# IsolationSheet.net
KiCad netlist of a schematic drawn in Altium Designer
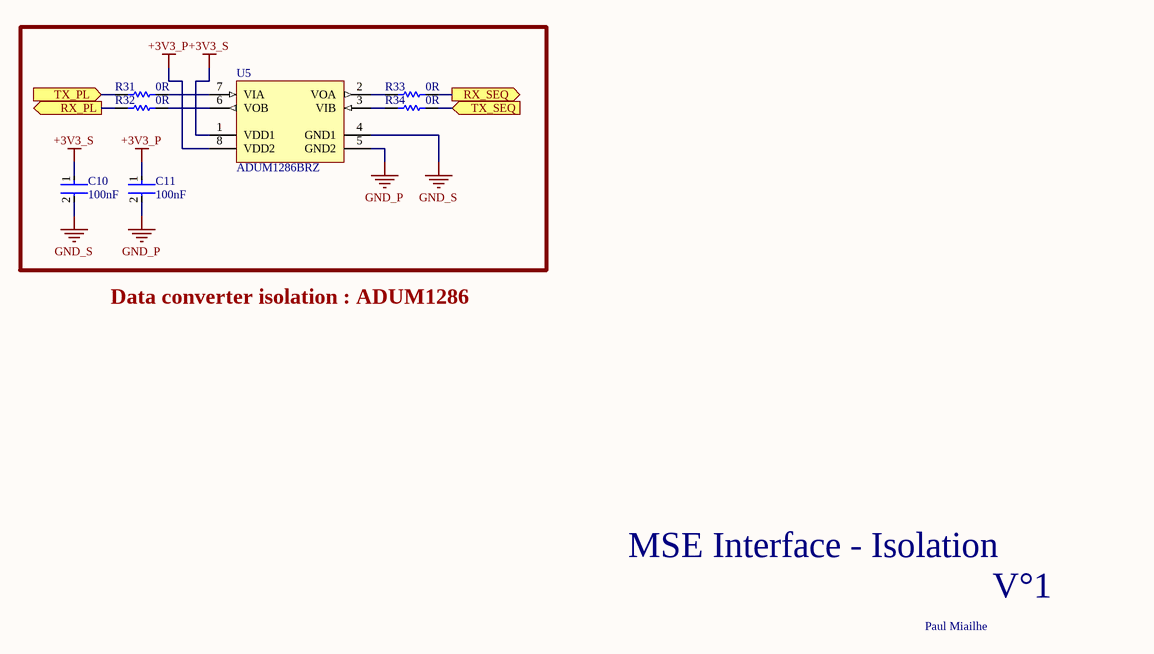
[diagram p0: IsolationSheet.SchDoc]

(export (version "E")
  (design (tool "Eeschema 10.0.6"))
  (components
    (comp (ref "C10")
      (value "CGA3E2X7R1E104K080AA")
      (footprint "FP-CGA3E-0_3-0_1-MFG")
      (description "Cap Ceramic 100nF 25V X7R 10% Pad SMD 0603 +125°C Automotive T/R")
      (fields
        (field (name "CAPACITANCE") "100nF")
        (field (name "TOLERANCE") "10%")
        (field (name "MANUFACTURER") "TDK")
      )
      (libsource (lib "Altium Content Vault") (part "b4654b650e69147ec39a6b967a45e02"))
    )
    (comp (ref "C11")
      (value "CGA3E2X7R1E104K080AA")
      (footprint "FP-CGA3E-0_3-0_1-MFG")
      (description "Cap Ceramic 100nF 25V X7R 10% Pad SMD 0603 +125°C Automotive T/R")
      (fields
        (field (name "CAPACITANCE") "100nF")
        (field (name "TOLERANCE") "10%")
        (field (name "MANUFACTURER") "TDK")
      )
      (libsource (lib "Altium Content Vault") (part "b4654b650e69147ec39a6b967a45e02"))
    )
    (comp (ref "R31")
      (value "RC0603JR-070RL")
      (footprint "RESC1608X55X25ML10T15")
      (description "Chip Resistor, 0 Ohm, +/- 5%, 0.1 W, -55 to 155 degC, 0603 (1608 Metric), RoHS, Tape and Reel")
      (fields
        (field (name "TOLERANCE") "5%")
        (field (name "RESISTANCE") "0R")
        (field (name "MANUFACTURER") "Yageo")
      )
      (libsource (lib "Altium Content Vault") (part "RES-2"))
    )
    (comp (ref "R32")
      (value "RC0603JR-070RL")
      (footprint "RESC1608X55X25ML10T15")
      (description "Chip Resistor, 0 Ohm, +/- 5%, 0.1 W, -55 to 155 degC, 0603 (1608 Metric), RoHS, Tape and Reel")
      (fields
        (field (name "TOLERANCE") "5%")
        (field (name "RESISTANCE") "0R")
        (field (name "MANUFACTURER") "Yageo")
      )
      (libsource (lib "Altium Content Vault") (part "RES-2"))
    )
    (comp (ref "R33")
      (value "RC0603JR-070RL")
      (footprint "RESC1608X55X25ML10T15")
      (description "Chip Resistor, 0 Ohm, +/- 5%, 0.1 W, -55 to 155 degC, 0603 (1608 Metric), RoHS, Tape and Reel")
      (fields
        (field (name "TOLERANCE") "5%")
        (field (name "RESISTANCE") "0R")
        (field (name "MANUFACTURER") "Yageo")
      )
      (libsource (lib "Altium Content Vault") (part "RES-2"))
    )
    (comp (ref "R34")
      (value "RC0603JR-070RL")
      (footprint "RESC1608X55X25ML10T15")
      (description "Chip Resistor, 0 Ohm, +/- 5%, 0.1 W, -55 to 155 degC, 0603 (1608 Metric), RoHS, Tape and Reel")
      (fields
        (field (name "TOLERANCE") "5%")
        (field (name "RESISTANCE") "0R")
        (field (name "MANUFACTURER") "Yageo")
      )
      (libsource (lib "Altium Content Vault") (part "RES-2"))
    )
    (comp (ref "U5")
      (value "ADUM1286BRZ")
      (footprint "ADI-R-8_M")
      (fields (field (name "MANUFACTURER") "Analog Devices"))
      (libsource (lib "Altium Content Vault") (part "ADI-ADUM1286-R-8"))
    )
  )
  (nets
    (net (code "1") (name "+3V3_P") (class "Default")
      (node (ref "C11") (pin "1") (pinfunction "1_1") (pintype "passive"))
      (node (ref "U5") (pin "8") (pinfunction "VDD2_8") (pintype "power_in"))
    )
    (net (code "2") (name "+3V3_S") (class "Default")
      (node (ref "C10") (pin "1") (pinfunction "1_1") (pintype "passive"))
      (node (ref "U5") (pin "1") (pinfunction "VDD1_1") (pintype "power_in"))
    )
    (net (code "3") (name "/RX_PL") (class "Default")
      (node (ref "R32") (pin "2") (pinfunction "2_2") (pintype "passive"))
    )
    (net (code "4") (name "/RX_SEQ") (class "Default")
      (node (ref "R33") (pin "1") (pinfunction "1_1") (pintype "passive"))
    )
    (net (code "5") (name "/TX_PL") (class "Default")
      (node (ref "R31") (pin "2") (pinfunction "2_2") (pintype "passive"))
    )
    (net (code "6") (name "/TX_SEQ") (class "Default")
      (node (ref "R34") (pin "1") (pinfunction "1_1") (pintype "passive"))
    )
    (net (code "7") (name "GND_P") (class "Default")
      (node (ref "C11") (pin "2") (pinfunction "2_2") (pintype "passive"))
      (node (ref "U5") (pin "5") (pinfunction "GND2_5") (pintype "power_in"))
    )
    (net (code "8") (name "GND_S") (class "Default")
      (node (ref "C10") (pin "2") (pinfunction "2_2") (pintype "passive"))
      (node (ref "U5") (pin "4") (pinfunction "GND1_4") (pintype "power_in"))
    )
    (net (code "9") (name "Net-(U5-VIA)") (class "Default")
      (node (ref "R31") (pin "1") (pinfunction "1_1") (pintype "passive"))
      (node (ref "U5") (pin "7") (pinfunction "VIA_7") (pintype "input"))
    )
    (net (code "10") (name "Net-(U5-VIB)") (class "Default")
      (node (ref "R34") (pin "2") (pinfunction "2_2") (pintype "passive"))
      (node (ref "U5") (pin "3") (pinfunction "VIB_3") (pintype "input"))
    )
    (net (code "11") (name "Net-(U5-VOA)") (class "Default")
      (node (ref "R33") (pin "2") (pinfunction "2_2") (pintype "passive"))
      (node (ref "U5") (pin "2") (pinfunction "VOA_2") (pintype "output"))
    )
    (net (code "12") (name "Net-(U5-VOB)") (class "Default")
      (node (ref "R32") (pin "1") (pinfunction "1_1") (pintype "passive"))
      (node (ref "U5") (pin "6") (pinfunction "VOB_6") (pintype "output"))
    )
  )
)
